# SP2.net
KiCad netlist of a schematic drawn in EAGLE
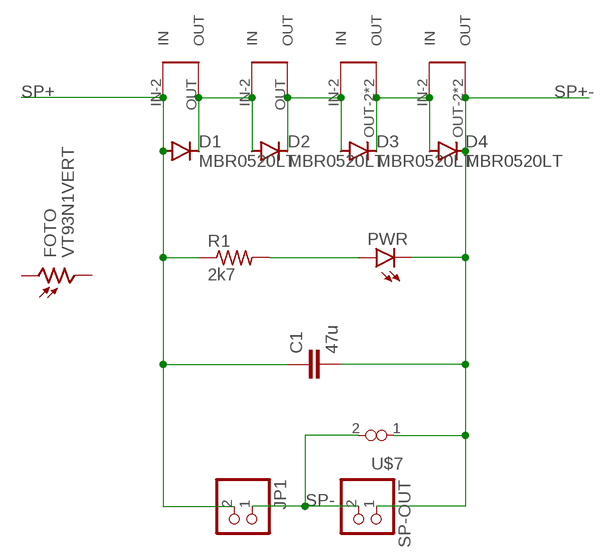
[diagram p0: schematic, sheet 1]

(export (version "E")
  (design (tool "Eeschema 10.0.6"))
  (components
    (comp (ref "C1")
      (value "47u")
      (footprint "eagle-import:C1210")
      (libsource (lib "eagle-import") (part "C-EUC1210"))
    )
    (comp (ref "D1")
      (value "MBR0520LT")
      (footprint "eagle-import:SOD123")
      (libsource (lib "eagle-import") (part "MBR0520LT"))
    )
    (comp (ref "D2")
      (value "MBR0520LT")
      (footprint "eagle-import:SOD123")
      (libsource (lib "eagle-import") (part "MBR0520LT"))
    )
    (comp (ref "D3")
      (value "MBR0520LT")
      (footprint "eagle-import:SOD123")
      (libsource (lib "eagle-import") (part "MBR0520LT"))
    )
    (comp (ref "D4")
      (value "MBR0520LT")
      (footprint "eagle-import:SOD123")
      (libsource (lib "eagle-import") (part "MBR0520LT"))
    )
    (comp (ref "FOTO")
      (value "VT93N1VERT")
      (footprint "eagle-import:VT93N1-VERT")
      (libsource (lib "eagle-import") (part "VT93N1VERT"))
    )
    (comp (ref "JP1")
      (value "PINHD-1X2")
      (footprint "eagle-import:1X02")
      (libsource (lib "eagle-import") (part "PINHD-1X2"))
    )
    (comp (ref "PWR")
      (value "LEDCHIP-LED0603")
      (footprint "eagle-import:CHIP-LED0603")
      (libsource (lib "eagle-import") (part "LEDCHIP-LED0603"))
    )
    (comp (ref "R1")
      (value "2k7")
      (footprint "eagle-import:R0603")
      (libsource (lib "eagle-import") (part "R-US_R0603"))
    )
    (comp (ref "SP-OUT")
      (value "PINHD-1X2")
      (footprint "eagle-import:1X02")
      (libsource (lib "eagle-import") (part "PINHD-1X2"))
    )
    (comp (ref "U$1")
      (value "SOLAR-2_1")
      (footprint "eagle-import:SOLAR_1-2")
      (libsource (lib "eagle-import") (part "SOLAR-2_1"))
    )
    (comp (ref "U$2")
      (value "SOLAR-2_1")
      (footprint "eagle-import:SOLAR_1-2")
      (libsource (lib "eagle-import") (part "SOLAR-2_1"))
    )
    (comp (ref "U$3")
      (value "SOLAR-2_0")
      (footprint "eagle-import:SOLAR_0-2")
      (libsource (lib "eagle-import") (part "SOLAR-2_0"))
    )
    (comp (ref "U$4")
      (value "SOLAR-2_0")
      (footprint "eagle-import:SOLAR_0-2")
      (libsource (lib "eagle-import") (part "SOLAR-2_0"))
    )
    (comp (ref "U$7")
      (value "VIAS-CONNECT")
      (footprint "eagle-import:VIAS-CONNECT")
      (libsource (lib "eagle-import") (part "VIAS-CONNECT"))
    )
  )
  (nets
    (net (code "1") (name "/SP+") (class "Default")
      (node (ref "C1") (pin "1") (pinfunction "1_1") (pintype "passive"))
      (node (ref "D1") (pin "A") (pinfunction "A_A") (pintype "passive"))
      (node (ref "JP1") (pin "2") (pinfunction "2_2") (pintype "passive"))
      (node (ref "R1") (pin "1") (pinfunction "1_1") (pintype "passive"))
      (node (ref "U$1") (pin "IN-2") (pinfunction "IN_IN-2") (pintype "bidirectional"))
    )
    (net (code "2") (name "/SP+-") (class "Default")
      (node (ref "C1") (pin "2") (pinfunction "2_2") (pintype "passive"))
      (node (ref "D4") (pin "C") (pinfunction "C_C") (pintype "passive"))
      (node (ref "PWR") (pin "C") (pinfunction "C_C") (pintype "passive"))
      (node (ref "SP-OUT") (pin "1") (pinfunction "1_1") (pintype "passive"))
      (node (ref "U$4") (pin "OUT-2") (pinfunction "OUT_OUT-2") (pintype "bidirectional"))
      (node (ref "U$4") (pin "OUT-21") (pinfunction "OUT_OUT-21") (pintype "bidirectional"))
      (node (ref "U$7") (pin "1") (pinfunction "1_1") (pintype "passive"))
    )
    (net (code "3") (name "/SP-") (class "Default")
      (node (ref "JP1") (pin "1") (pinfunction "1_1") (pintype "passive"))
      (node (ref "SP-OUT") (pin "2") (pinfunction "2_2") (pintype "passive"))
      (node (ref "U$7") (pin "2") (pinfunction "2_2") (pintype "passive"))
    )
    (net (code "4") (name "Net-(PWR-PadA)") (class "Default")
      (node (ref "PWR") (pin "A") (pinfunction "A_A") (pintype "passive"))
      (node (ref "R1") (pin "2") (pinfunction "2_2") (pintype "passive"))
    )
    (net (code "5") (name "Net-(U$2-IN)") (class "Default")
      (node (ref "D1") (pin "C") (pinfunction "C_C") (pintype "passive"))
      (node (ref "D2") (pin "A") (pinfunction "A_A") (pintype "passive"))
      (node (ref "U$1") (pin "OUT") (pinfunction "OUT_OUT") (pintype "bidirectional"))
      (node (ref "U$2") (pin "IN-2") (pinfunction "IN_IN-2") (pintype "bidirectional"))
    )
    (net (code "6") (name "Net-(U$3-IN)") (class "Default")
      (node (ref "D2") (pin "C") (pinfunction "C_C") (pintype "passive"))
      (node (ref "D3") (pin "A") (pinfunction "A_A") (pintype "passive"))
      (node (ref "U$2") (pin "OUT") (pinfunction "OUT_OUT") (pintype "bidirectional"))
      (node (ref "U$3") (pin "IN-2") (pinfunction "IN_IN-2") (pintype "bidirectional"))
    )
    (net (code "7") (name "Net-(U$4-IN)") (class "Default")
      (node (ref "D3") (pin "C") (pinfunction "C_C") (pintype "passive"))
      (node (ref "D4") (pin "A") (pinfunction "A_A") (pintype "passive"))
      (node (ref "U$3") (pin "OUT-2") (pinfunction "OUT_OUT-2") (pintype "bidirectional"))
      (node (ref "U$3") (pin "OUT-21") (pinfunction "OUT_OUT-21") (pintype "bidirectional"))
      (node (ref "U$4") (pin "IN-2") (pinfunction "IN_IN-2") (pintype "bidirectional"))
    )
    (net (code "8") (name "unconnected-(FOTO-1-PadP$1)") (class "Default")
      (node (ref "FOTO") (pin "P$1") (pinfunction "1_P$1") (pintype "passive"))
    )
    (net (code "9") (name "unconnected-(FOTO-2-PadP$2)") (class "Default")
      (node (ref "FOTO") (pin "P$2") (pinfunction "2_P$2") (pintype "passive"))
    )
  )
)
